# LED_power-supply.net
KiCad netlist of a schematic drawn in EAGLE
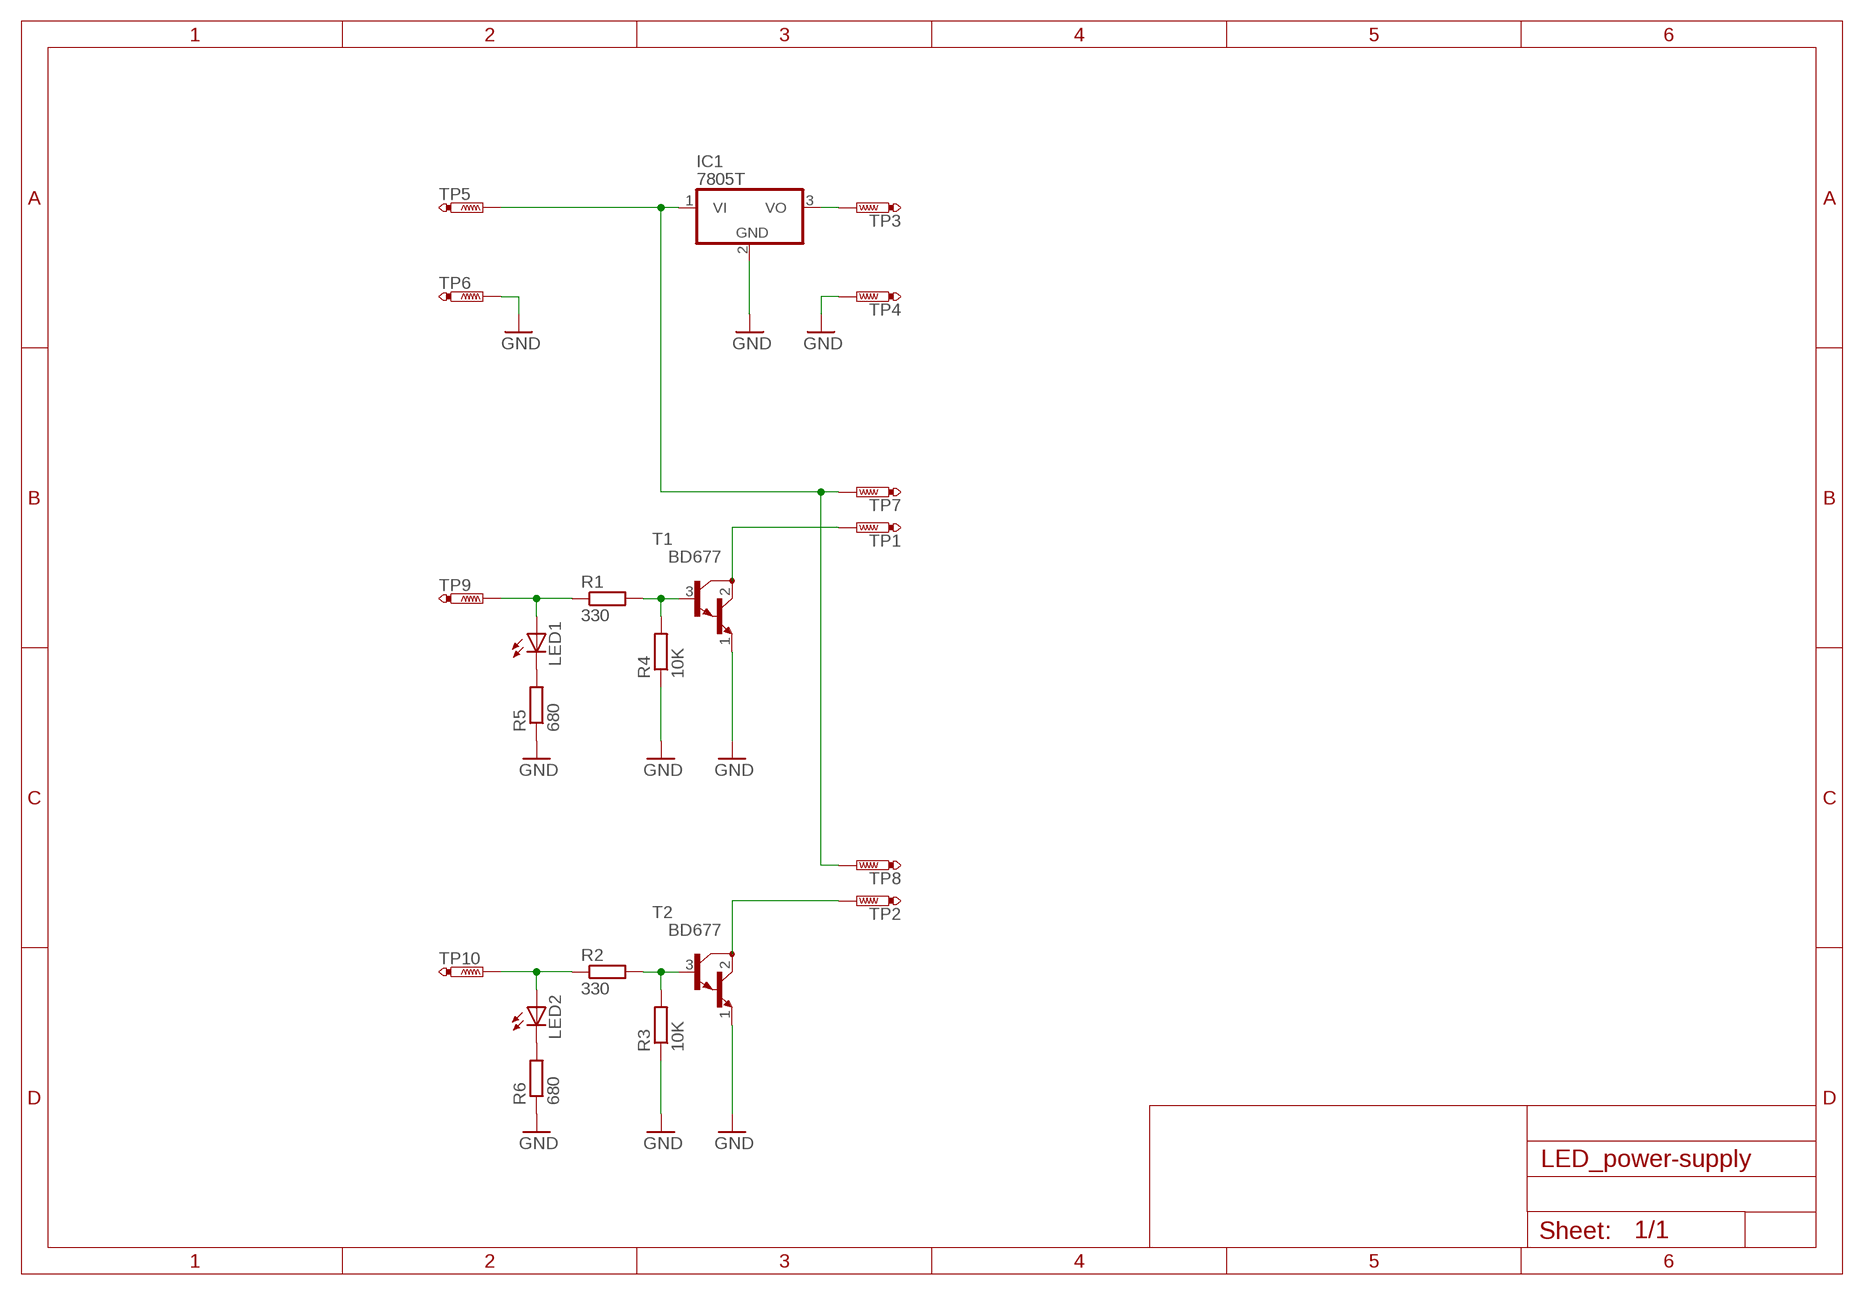
[diagram p0: schematic, sheet 1]

(export (version "E")
  (design (tool "Eeschema 10.0.6"))
  (components
    (comp (ref "IC1")
      (value "7805T")
      (footprint "eagle-import:TO220H")
      (libsource (lib "eagle-import") (part "78T05"))
    )
    (comp (ref "LED1")
      (value "LED3MM")
      (footprint "eagle-import:LED3MM")
      (libsource (lib "eagle-import") (part "LED3MM"))
    )
    (comp (ref "LED2")
      (value "LED3MM")
      (footprint "eagle-import:LED3MM")
      (libsource (lib "eagle-import") (part "LED3MM"))
    )
    (comp (ref "R1")
      (value "330")
      (footprint "eagle-import:0207_10")
      (libsource (lib "eagle-import") (part "R-EU_0207/10"))
    )
    (comp (ref "R2")
      (value "330")
      (footprint "eagle-import:0207_10")
      (libsource (lib "eagle-import") (part "R-EU_0207/10"))
    )
    (comp (ref "R3")
      (value "10K")
      (footprint "eagle-import:0207_10")
      (libsource (lib "eagle-import") (part "R-EU_0207/10"))
    )
    (comp (ref "R4")
      (value "10K")
      (footprint "eagle-import:0207_10")
      (libsource (lib "eagle-import") (part "R-EU_0207/10"))
    )
    (comp (ref "R5")
      (value "680")
      (footprint "eagle-import:0207_10")
      (libsource (lib "eagle-import") (part "R-EU_0207/10"))
    )
    (comp (ref "R6")
      (value "680")
      (footprint "eagle-import:0207_10")
      (libsource (lib "eagle-import") (part "R-EU_0207/10"))
    )
    (comp (ref "T1")
      (value "BD677")
      (footprint "eagle-import:TO126")
      (libsource (lib "eagle-import") (part "BD677"))
    )
    (comp (ref "T2")
      (value "BD677")
      (footprint "eagle-import:TO126")
      (libsource (lib "eagle-import") (part "BD677"))
    )
    (comp (ref "TP1")
      (value "PTR1PAD1-17")
      (footprint "eagle-import:P1-17")
      (libsource (lib "eagle-import") (part "PTR1PAD1-17"))
    )
    (comp (ref "TP2")
      (value "PTR1PAD1-17")
      (footprint "eagle-import:P1-17")
      (libsource (lib "eagle-import") (part "PTR1PAD1-17"))
    )
    (comp (ref "TP3")
      (value "PTR1PAD1-17")
      (footprint "eagle-import:P1-17")
      (libsource (lib "eagle-import") (part "PTR1PAD1-17"))
    )
    (comp (ref "TP4")
      (value "PTR1PAD1-17")
      (footprint "eagle-import:P1-17")
      (libsource (lib "eagle-import") (part "PTR1PAD1-17"))
    )
    (comp (ref "TP5")
      (value "PTR1PAD1-17")
      (footprint "eagle-import:P1-17")
      (libsource (lib "eagle-import") (part "PTR1PAD1-17"))
    )
    (comp (ref "TP6")
      (value "PTR1PAD1-17")
      (footprint "eagle-import:P1-17")
      (libsource (lib "eagle-import") (part "PTR1PAD1-17"))
    )
    (comp (ref "TP7")
      (value "PTR1PAD1-17")
      (footprint "eagle-import:P1-17")
      (libsource (lib "eagle-import") (part "PTR1PAD1-17"))
    )
    (comp (ref "TP8")
      (value "PTR1PAD1-17")
      (footprint "eagle-import:P1-17")
      (libsource (lib "eagle-import") (part "PTR1PAD1-17"))
    )
    (comp (ref "TP9")
      (value "PTR1PAD1-17")
      (footprint "eagle-import:P1-17")
      (libsource (lib "eagle-import") (part "PTR1PAD1-17"))
    )
    (comp (ref "TP10")
      (value "PTR1PAD1-17")
      (footprint "eagle-import:P1-17")
      (libsource (lib "eagle-import") (part "PTR1PAD1-17"))
    )
  )
  (nets
    (net (code "1") (name "GND") (class "Default")
      (node (ref "IC1") (pin "2") (pinfunction "GND_2") (pintype "passive"))
      (node (ref "R3") (pin "1") (pinfunction "1_1") (pintype "passive"))
      (node (ref "R4") (pin "1") (pinfunction "1_1") (pintype "passive"))
      (node (ref "R5") (pin "1") (pinfunction "1_1") (pintype "passive"))
      (node (ref "R6") (pin "1") (pinfunction "1_1") (pintype "passive"))
      (node (ref "T1") (pin "1") (pinfunction "E_1") (pintype "passive"))
      (node (ref "T2") (pin "1") (pinfunction "E_1") (pintype "passive"))
      (node (ref "TP4") (pin "TP") (pinfunction "TP_TP") (pintype "input"))
      (node (ref "TP6") (pin "TP") (pinfunction "TP_TP") (pintype "input"))
    )
    (net (code "2") (name "Net-(IC1-VI)") (class "Default")
      (node (ref "IC1") (pin "1") (pinfunction "VI_1") (pintype "input"))
      (node (ref "TP5") (pin "TP") (pinfunction "TP_TP") (pintype "input"))
      (node (ref "TP7") (pin "TP") (pinfunction "TP_TP") (pintype "input"))
      (node (ref "TP8") (pin "TP") (pinfunction "TP_TP") (pintype "input"))
    )
    (net (code "3") (name "Net-(IC1-VO)") (class "Default")
      (node (ref "IC1") (pin "3") (pinfunction "VO_3") (pintype "passive"))
      (node (ref "TP3") (pin "TP") (pinfunction "TP_TP") (pintype "input"))
    )
    (net (code "4") (name "Net-(LED1-C)") (class "Default")
      (node (ref "LED1") (pin "K") (pinfunction "C_K") (pintype "passive"))
      (node (ref "R5") (pin "2") (pinfunction "2_2") (pintype "passive"))
    )
    (net (code "5") (name "Net-(LED1-PadA)") (class "Default")
      (node (ref "LED1") (pin "A") (pinfunction "A_A") (pintype "passive"))
      (node (ref "R1") (pin "1") (pinfunction "1_1") (pintype "passive"))
      (node (ref "TP9") (pin "TP") (pinfunction "TP_TP") (pintype "input"))
    )
    (net (code "6") (name "Net-(LED2-C)") (class "Default")
      (node (ref "LED2") (pin "K") (pinfunction "C_K") (pintype "passive"))
      (node (ref "R6") (pin "2") (pinfunction "2_2") (pintype "passive"))
    )
    (net (code "7") (name "Net-(LED2-PadA)") (class "Default")
      (node (ref "LED2") (pin "A") (pinfunction "A_A") (pintype "passive"))
      (node (ref "R2") (pin "1") (pinfunction "1_1") (pintype "passive"))
      (node (ref "TP10") (pin "TP") (pinfunction "TP_TP") (pintype "input"))
    )
    (net (code "8") (name "Net-(T1-B)") (class "Default")
      (node (ref "R1") (pin "2") (pinfunction "2_2") (pintype "passive"))
      (node (ref "R4") (pin "2") (pinfunction "2_2") (pintype "passive"))
      (node (ref "T1") (pin "3") (pinfunction "B_3") (pintype "passive"))
    )
    (net (code "9") (name "Net-(T1-C)") (class "Default")
      (node (ref "T1") (pin "2") (pinfunction "C_2") (pintype "passive"))
      (node (ref "TP1") (pin "TP") (pinfunction "TP_TP") (pintype "input"))
    )
    (net (code "10") (name "Net-(T2-B)") (class "Default")
      (node (ref "R2") (pin "2") (pinfunction "2_2") (pintype "passive"))
      (node (ref "R3") (pin "2") (pinfunction "2_2") (pintype "passive"))
      (node (ref "T2") (pin "3") (pinfunction "B_3") (pintype "passive"))
    )
    (net (code "11") (name "Net-(T2-C)") (class "Default")
      (node (ref "T2") (pin "2") (pinfunction "C_2") (pintype "passive"))
      (node (ref "TP2") (pin "TP") (pinfunction "TP_TP") (pintype "input"))
    )
  )
)
